# IntegratedSensor.net
KiCad netlist of a schematic drawn in EAGLE
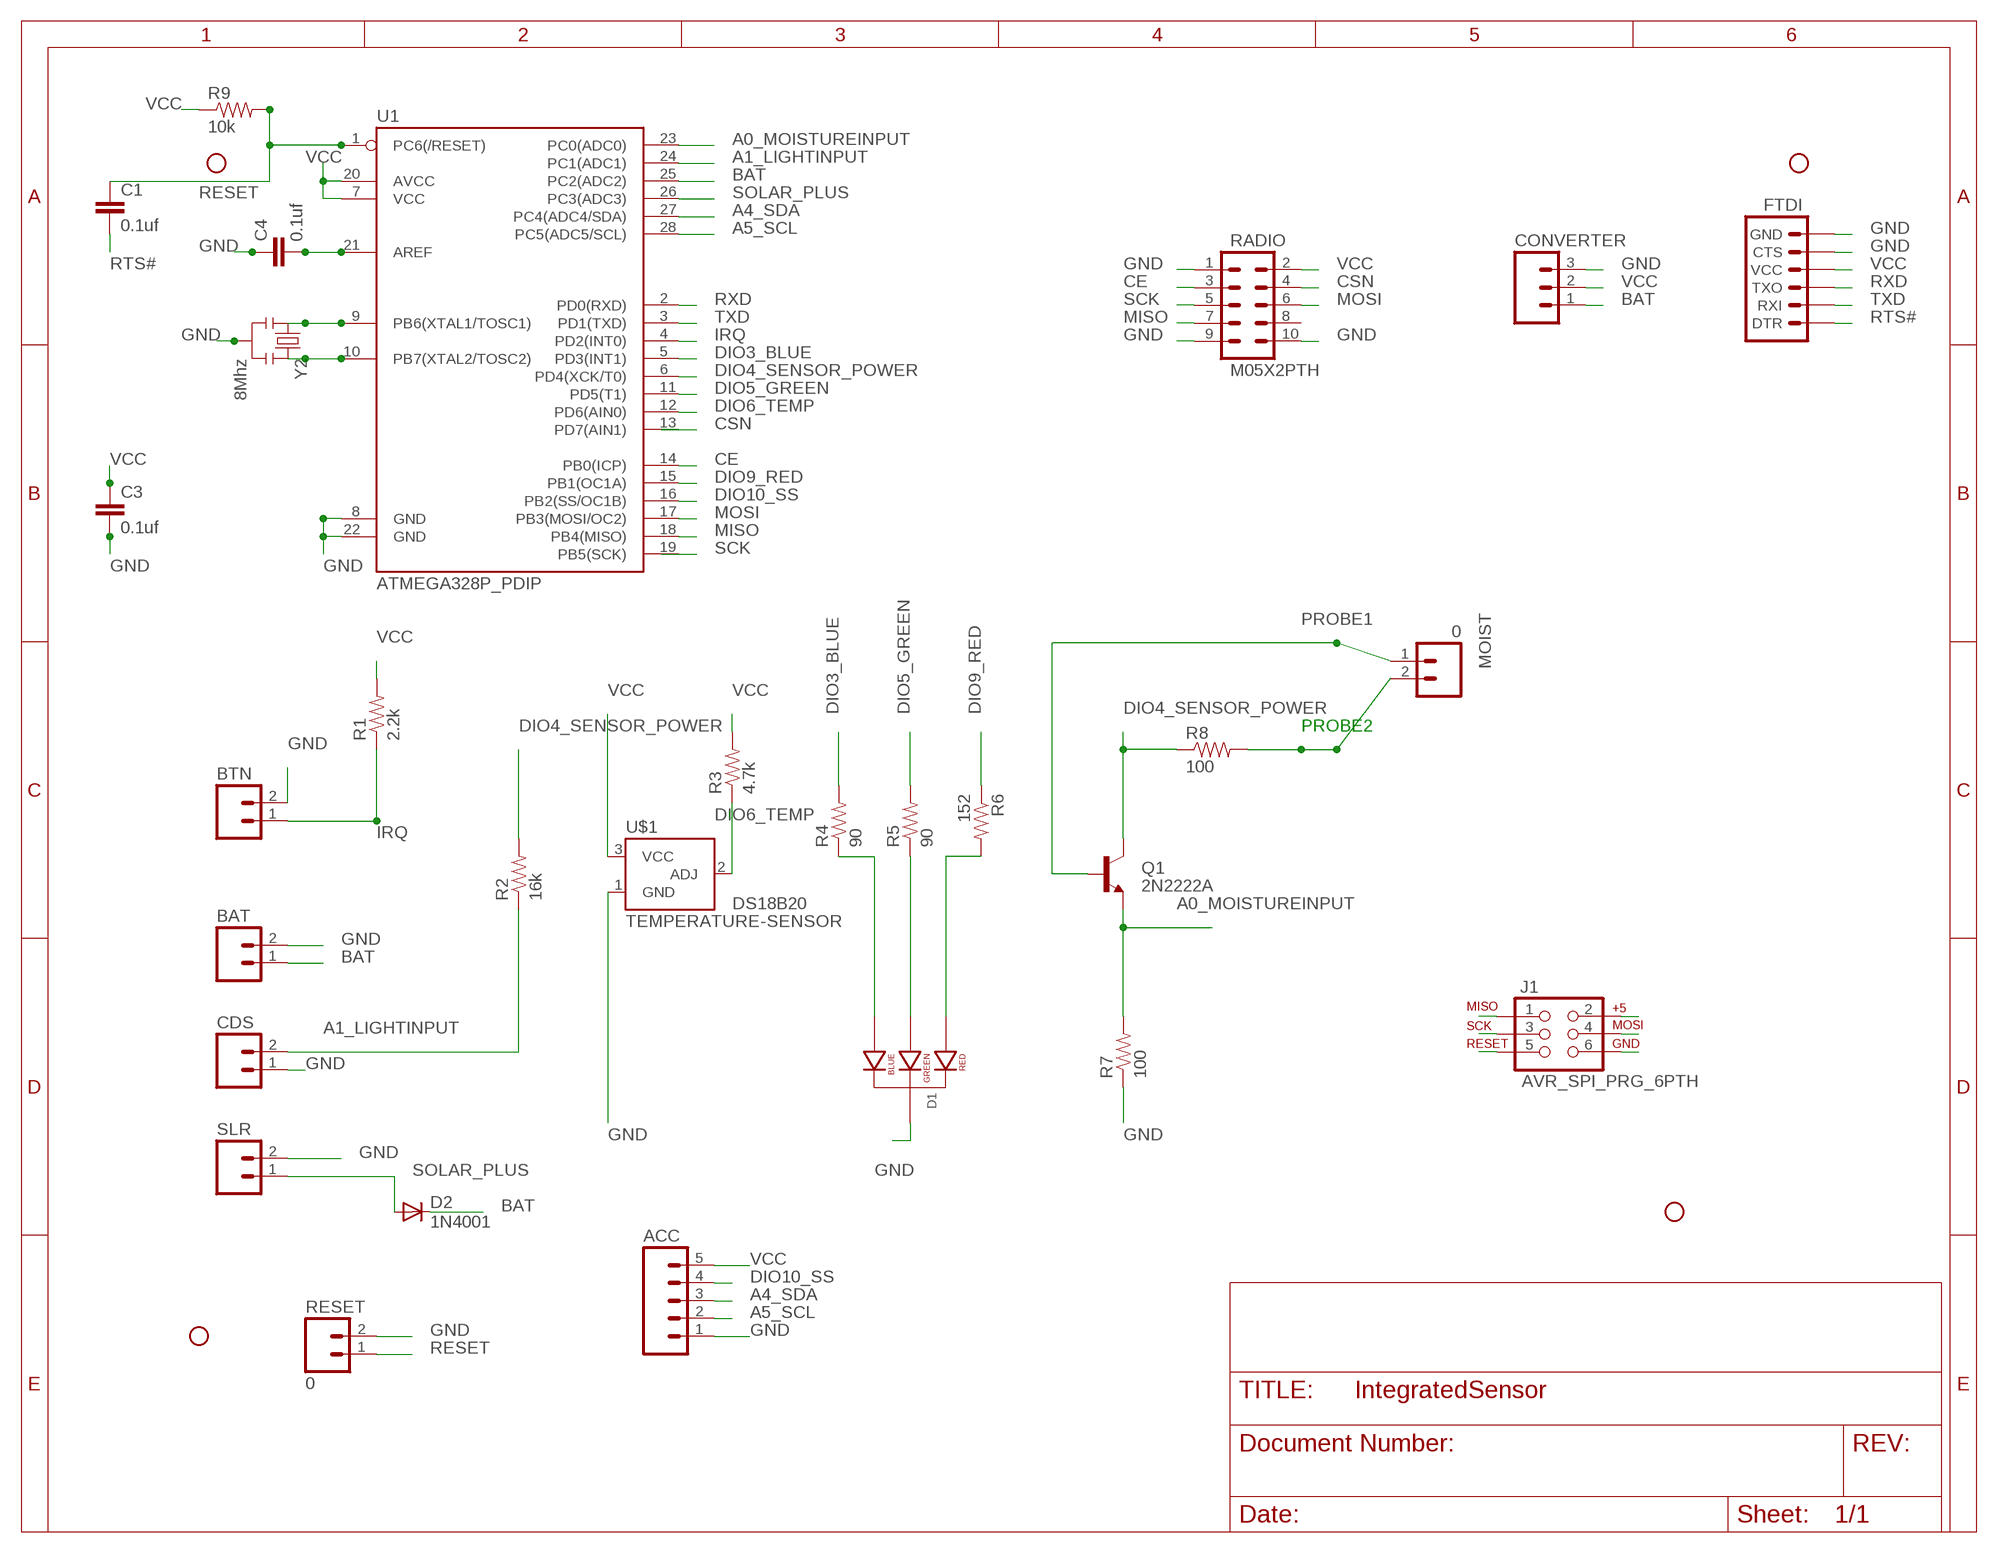
[diagram p0: schematic, sheet 1]

(export (version "E")
  (design (tool "Eeschema 10.0.6"))
  (components
    (comp (ref "ACC")
      (value "M05PTH")
      (footprint "eagle-import:1X05")
      (libsource (lib "eagle-import") (part "M05PTH"))
    )
    (comp (ref "BAT")
      (value "M02PTH")
      (footprint "eagle-import:1X02")
      (libsource (lib "eagle-import") (part "M02PTH"))
    )
    (comp (ref "BTN")
      (value "M02PTH")
      (footprint "eagle-import:1X02")
      (libsource (lib "eagle-import") (part "M02PTH"))
    )
    (comp (ref "C1")
      (value "0.1uf")
      (footprint "eagle-import:CAP-PTH-SMALL")
      (libsource (lib "eagle-import") (part "CAPPTH"))
    )
    (comp (ref "C3")
      (value "0.1uf")
      (footprint "eagle-import:CAP-PTH-SMALL")
      (libsource (lib "eagle-import") (part "CAPPTH"))
    )
    (comp (ref "C4")
      (value "0.1uf")
      (footprint "eagle-import:CAP-PTH-SMALL")
      (libsource (lib "eagle-import") (part "CAPPTH"))
    )
    (comp (ref "CDS")
      (value "M02PTH")
      (footprint "eagle-import:1X02")
      (libsource (lib "eagle-import") (part "M02PTH"))
    )
    (comp (ref "CONVERTER")
      (value "M03PTH")
      (footprint "eagle-import:1X03")
      (libsource (lib "eagle-import") (part "M03PTH"))
    )
    (comp (ref "D1")
      (value "LED-RGB-CC-THRUCLEAR")
      (footprint "eagle-import:LED-RGB-THRU")
      (libsource (lib "eagle-import") (part "LED-RGB-CC-THRUCLEAR"))
    )
    (comp (ref "D2")
      (value "1N4001")
      (footprint "eagle-import:DIODE-1N4001")
      (libsource (lib "eagle-import") (part "DIODEPTH"))
    )
    (comp (ref "FTDI")
      (value "ARDUINO_SERIAL_PROGRAMPTH")
      (footprint "eagle-import:1X06")
      (libsource (lib "eagle-import") (part "ARDUINO_SERIAL_PROGRAMPTH"))
    )
    (comp (ref "J1")
      (value "AVR_SPI_PRG_6PTH")
      (footprint "eagle-import:2X3")
      (libsource (lib "eagle-import") (part "AVR_SPI_PRG_6PTH"))
    )
    (comp (ref "MOIST")
      (value "0")
      (footprint "eagle-import:1X02")
      (libsource (lib "eagle-import") (part "M02PTH"))
    )
    (comp (ref "Q1")
      (value "2N2222A")
      (footprint "eagle-import:TO-92-AMMO")
      (libsource (lib "eagle-import") (part "TRANSISTOR_NPNTO-92-AMMO"))
    )
    (comp (ref "R1")
      (value "2.2k")
      (footprint "eagle-import:1_6W-RES")
      (libsource (lib "eagle-import") (part "RESISTORPTH-1/6W"))
    )
    (comp (ref "R2")
      (value "16k")
      (footprint "eagle-import:1_6W-RES")
      (libsource (lib "eagle-import") (part "RESISTORPTH-1/6W"))
    )
    (comp (ref "R3")
      (value "4.7k")
      (footprint "eagle-import:1_6W-RES")
      (libsource (lib "eagle-import") (part "RESISTORPTH-1/6W"))
    )
    (comp (ref "R4")
      (value "90")
      (footprint "eagle-import:1_6W-RES")
      (libsource (lib "eagle-import") (part "RESISTORPTH-1/6W"))
    )
    (comp (ref "R5")
      (value "90")
      (footprint "eagle-import:1_6W-RES")
      (libsource (lib "eagle-import") (part "RESISTORPTH-1/6W"))
    )
    (comp (ref "R6")
      (value "152")
      (footprint "eagle-import:1_6W-RES")
      (libsource (lib "eagle-import") (part "RESISTORPTH-1/6W"))
    )
    (comp (ref "R7")
      (value "100")
      (footprint "eagle-import:1_6W-RES")
      (libsource (lib "eagle-import") (part "RESISTORPTH-1/6W"))
    )
    (comp (ref "R8")
      (value "100")
      (footprint "eagle-import:1_6W-RES")
      (libsource (lib "eagle-import") (part "RESISTORPTH-1/6W"))
    )
    (comp (ref "R9")
      (value "10k")
      (footprint "eagle-import:1_6W-RES")
      (libsource (lib "eagle-import") (part "RESISTORPTH-1/6W"))
    )
    (comp (ref "RADIO")
      (value "M05X2PTH")
      (footprint "eagle-import:AVR_ICSP")
      (libsource (lib "eagle-import") (part "M05X2PTH"))
    )
    (comp (ref "RESET")
      (value "0")
      (footprint "eagle-import:1X02")
      (libsource (lib "eagle-import") (part "M02PTH"))
    )
    (comp (ref "SLR")
      (value "M02PTH")
      (footprint "eagle-import:1X02")
      (libsource (lib "eagle-import") (part "M02PTH"))
    )
    (comp (ref "STANDOFF1")
      (value "STAND-OFF")
      (footprint "eagle-import:STAND-OFF")
      (libsource (lib "eagle-import") (part "STAND-OFF"))
    )
    (comp (ref "STANDOFF2")
      (value "STAND-OFF")
      (footprint "eagle-import:STAND-OFF")
      (libsource (lib "eagle-import") (part "STAND-OFF"))
    )
    (comp (ref "STANDOFF3")
      (value "STAND-OFF")
      (footprint "eagle-import:STAND-OFF")
      (libsource (lib "eagle-import") (part "STAND-OFF"))
    )
    (comp (ref "STANDOFF4")
      (value "STAND-OFF")
      (footprint "eagle-import:STAND-OFF")
      (libsource (lib "eagle-import") (part "STAND-OFF"))
    )
    (comp (ref "U$1")
      (value "TEMPERATURE-SENSOR")
      (footprint "eagle-import:TO-92")
      (fields (field (name "PARTNAME") "DS18B20"))
      (libsource (lib "eagle-import") (part "TEMPERATURE-SENSOR"))
    )
    (comp (ref "U1")
      (value "ATMEGA328P_PDIP")
      (footprint "eagle-import:DIL28-3")
      (libsource (lib "eagle-import") (part "ATMEGA328P_PDIP"))
    )
    (comp (ref "Y2")
      (value "8Mhz")
      (footprint "eagle-import:RESONATOR-PTH")
      (libsource (lib "eagle-import") (part "RESONATORPTH"))
    )
  )
  (nets
    (net (code "1") (name "/A0_MOISTUREINPUT") (class "Default")
      (node (ref "Q1") (pin "1") (pinfunction "E_1") (pintype "passive"))
      (node (ref "R7") (pin "2") (pinfunction "2_2") (pintype "passive"))
      (node (ref "U1") (pin "23") (pinfunction "PC0(ADC0)_23") (pintype "bidirectional"))
    )
    (net (code "2") (name "/A1_LIGHTINPUT") (class "Default")
      (node (ref "CDS") (pin "2") (pinfunction "2_2") (pintype "passive"))
      (node (ref "R2") (pin "1") (pinfunction "1_1") (pintype "passive"))
      (node (ref "U1") (pin "24") (pinfunction "PC1(ADC1)_24") (pintype "bidirectional"))
    )
    (net (code "3") (name "/A4_SDA") (class "Default")
      (node (ref "ACC") (pin "3") (pinfunction "3_3") (pintype "passive"))
      (node (ref "U1") (pin "27") (pinfunction "PC4(ADC4/SDA)_27") (pintype "bidirectional"))
    )
    (net (code "4") (name "/A5_SCL") (class "Default")
      (node (ref "ACC") (pin "2") (pinfunction "2_2") (pintype "passive"))
      (node (ref "U1") (pin "28") (pinfunction "PC5(ADC5/SCL)_28") (pintype "bidirectional"))
    )
    (net (code "5") (name "/BAT") (class "Default")
      (node (ref "BAT") (pin "1") (pinfunction "1_1") (pintype "passive"))
      (node (ref "CONVERTER") (pin "1") (pinfunction "1_1") (pintype "passive"))
      (node (ref "D2") (pin "C") (pinfunction "C_C") (pintype "passive"))
      (node (ref "U1") (pin "25") (pinfunction "PC2(ADC2)_25") (pintype "bidirectional"))
    )
    (net (code "6") (name "/CE") (class "Default")
      (node (ref "RADIO") (pin "3") (pinfunction "3_3") (pintype "passive"))
      (node (ref "U1") (pin "14") (pinfunction "PB0(ICP)_14") (pintype "bidirectional"))
    )
    (net (code "7") (name "/CSN") (class "Default")
      (node (ref "RADIO") (pin "4") (pinfunction "4_4") (pintype "passive"))
    )
    (net (code "8") (name "/DIO3_BLUE") (class "Default")
      (node (ref "R4") (pin "2") (pinfunction "2_2") (pintype "passive"))
      (node (ref "U1") (pin "5") (pinfunction "PD3(INT1)_5") (pintype "bidirectional"))
    )
    (net (code "9") (name "/DIO4_SENSOR_POWER") (class "Default")
      (node (ref "Q1") (pin "3") (pinfunction "C_3") (pintype "passive"))
      (node (ref "R2") (pin "2") (pinfunction "2_2") (pintype "passive"))
      (node (ref "R8") (pin "1") (pinfunction "1_1") (pintype "passive"))
      (node (ref "U1") (pin "6") (pinfunction "PD4(XCK/T0)_6") (pintype "bidirectional"))
    )
    (net (code "10") (name "/DIO5_GREEN") (class "Default")
      (node (ref "R5") (pin "2") (pinfunction "2_2") (pintype "passive"))
      (node (ref "U1") (pin "11") (pinfunction "PD5(T1)_11") (pintype "bidirectional"))
    )
    (net (code "11") (name "/DIO6_TEMP") (class "Default")
      (node (ref "R3") (pin "1") (pinfunction "1_1") (pintype "passive"))
      (node (ref "U$1") (pin "2") (pinfunction "ADJ_2") (pintype "bidirectional"))
      (node (ref "U1") (pin "12") (pinfunction "PD6(AIN0)_12") (pintype "bidirectional"))
    )
    (net (code "12") (name "/DIO9_RED") (class "Default")
      (node (ref "R6") (pin "1") (pinfunction "1_1") (pintype "passive"))
      (node (ref "U1") (pin "15") (pinfunction "PB1(OC1A)_15") (pintype "bidirectional"))
    )
    (net (code "13") (name "/DIO10_SS") (class "Default")
      (node (ref "ACC") (pin "4") (pinfunction "4_4") (pintype "passive"))
      (node (ref "U1") (pin "16") (pinfunction "PB2(SS/OC1B)_16") (pintype "bidirectional"))
    )
    (net (code "14") (name "/GND") (class "Default")
      (node (ref "ACC") (pin "1") (pinfunction "1_1") (pintype "passive"))
      (node (ref "BAT") (pin "2") (pinfunction "2_2") (pintype "passive"))
      (node (ref "BTN") (pin "2") (pinfunction "2_2") (pintype "passive"))
      (node (ref "C3") (pin "2") (pinfunction "2_2") (pintype "passive"))
      (node (ref "C4") (pin "1") (pinfunction "1_1") (pintype "passive"))
      (node (ref "CDS") (pin "1") (pinfunction "1_1") (pintype "passive"))
      (node (ref "CONVERTER") (pin "3") (pinfunction "3_3") (pintype "passive"))
      (node (ref "D1") (pin "2") (pinfunction "CATHODE_2") (pintype "bidirectional"))
      (node (ref "FTDI") (pin "5") (pinfunction "CTS_5") (pintype "passive"))
      (node (ref "FTDI") (pin "6") (pinfunction "GND_6") (pintype "passive"))
      (node (ref "J1") (pin "6") (pinfunction "6_6") (pintype "passive"))
      (node (ref "R7") (pin "1") (pinfunction "1_1") (pintype "passive"))
      (node (ref "RADIO") (pin "1") (pinfunction "1_1") (pintype "passive"))
      (node (ref "RADIO") (pin "10") (pinfunction "10_10") (pintype "passive"))
      (node (ref "RADIO") (pin "9") (pinfunction "9_9") (pintype "passive"))
      (node (ref "RESET") (pin "2") (pinfunction "2_2") (pintype "passive"))
      (node (ref "SLR") (pin "2") (pinfunction "2_2") (pintype "passive"))
      (node (ref "U$1") (pin "1") (pinfunction "GND_1") (pintype "bidirectional"))
      (node (ref "U1") (pin "22") (pinfunction "GND_22") (pintype "bidirectional"))
      (node (ref "U1") (pin "8") (pinfunction "GND_8") (pintype "bidirectional"))
      (node (ref "Y2") (pin "2") (pinfunction "2_2") (pintype "passive"))
    )
    (net (code "15") (name "/IRQ") (class "Default")
      (node (ref "BTN") (pin "1") (pinfunction "1_1") (pintype "passive"))
      (node (ref "R1") (pin "1") (pinfunction "1_1") (pintype "passive"))
      (node (ref "U1") (pin "4") (pinfunction "PD2(INT0)_4") (pintype "bidirectional"))
    )
    (net (code "16") (name "/MISO") (class "Default")
      (node (ref "J1") (pin "1") (pinfunction "1_1") (pintype "passive"))
      (node (ref "RADIO") (pin "7") (pinfunction "7_7") (pintype "passive"))
      (node (ref "U1") (pin "18") (pinfunction "PB4(MISO)_18") (pintype "bidirectional"))
    )
    (net (code "17") (name "/MOSI") (class "Default")
      (node (ref "J1") (pin "4") (pinfunction "4_4") (pintype "passive"))
      (node (ref "RADIO") (pin "6") (pinfunction "6_6") (pintype "passive"))
      (node (ref "U1") (pin "17") (pinfunction "PB3(MOSI/OC2)_17") (pintype "bidirectional"))
    )
    (net (code "18") (name "/PROBE1") (class "Default")
      (node (ref "MOIST") (pin "1") (pinfunction "1_1") (pintype "passive"))
      (node (ref "Q1") (pin "2") (pinfunction "B_2") (pintype "passive"))
    )
    (net (code "19") (name "/PROBE2") (class "Default")
      (node (ref "MOIST") (pin "2") (pinfunction "2_2") (pintype "passive"))
      (node (ref "R8") (pin "2") (pinfunction "2_2") (pintype "passive"))
    )
    (net (code "20") (name "/RESET") (class "Default")
      (node (ref "C1") (pin "1") (pinfunction "1_1") (pintype "passive"))
      (node (ref "J1") (pin "5") (pinfunction "5_5") (pintype "passive"))
      (node (ref "R9") (pin "2") (pinfunction "2_2") (pintype "passive"))
      (node (ref "RESET") (pin "1") (pinfunction "1_1") (pintype "passive"))
      (node (ref "U1") (pin "1") (pinfunction "PC6(/RESET)_1") (pintype "bidirectional"))
    )
    (net (code "21") (name "/RTS#") (class "Default")
      (node (ref "C1") (pin "2") (pinfunction "2_2") (pintype "passive"))
      (node (ref "FTDI") (pin "1") (pinfunction "DTR_1") (pintype "passive"))
    )
    (net (code "22") (name "/RXD") (class "Default")
      (node (ref "FTDI") (pin "3") (pinfunction "TXO_3") (pintype "passive"))
      (node (ref "U1") (pin "2") (pinfunction "PD0(RXD)_2") (pintype "bidirectional"))
    )
    (net (code "23") (name "/SCK") (class "Default")
      (node (ref "J1") (pin "3") (pinfunction "3_3") (pintype "passive"))
      (node (ref "RADIO") (pin "5") (pinfunction "5_5") (pintype "passive"))
    )
    (net (code "24") (name "/SOLAR_PLUS") (class "Default")
      (node (ref "D2") (pin "A") (pinfunction "A_A") (pintype "passive"))
      (node (ref "SLR") (pin "1") (pinfunction "1_1") (pintype "passive"))
      (node (ref "U1") (pin "26") (pinfunction "PC3(ADC3)_26") (pintype "bidirectional"))
    )
    (net (code "25") (name "/TXD") (class "Default")
      (node (ref "FTDI") (pin "2") (pinfunction "RXI_2") (pintype "passive"))
      (node (ref "U1") (pin "3") (pinfunction "PD1(TXD)_3") (pintype "bidirectional"))
    )
    (net (code "26") (name "/VCC") (class "Default")
      (node (ref "ACC") (pin "5") (pinfunction "5_5") (pintype "passive"))
      (node (ref "C3") (pin "1") (pinfunction "1_1") (pintype "passive"))
      (node (ref "CONVERTER") (pin "2") (pinfunction "2_2") (pintype "passive"))
      (node (ref "FTDI") (pin "4") (pinfunction "VCC_4") (pintype "passive"))
      (node (ref "J1") (pin "2") (pinfunction "2_2") (pintype "passive"))
      (node (ref "R1") (pin "2") (pinfunction "2_2") (pintype "passive"))
      (node (ref "R3") (pin "2") (pinfunction "2_2") (pintype "passive"))
      (node (ref "R9") (pin "1") (pinfunction "1_1") (pintype "passive"))
      (node (ref "RADIO") (pin "2") (pinfunction "2_2") (pintype "passive"))
      (node (ref "U$1") (pin "3") (pinfunction "VCC_3") (pintype "bidirectional"))
      (node (ref "U1") (pin "20") (pinfunction "AVCC_20") (pintype "bidirectional"))
      (node (ref "U1") (pin "7") (pinfunction "VCC_7") (pintype "bidirectional"))
    )
    (net (code "27") (name "Net-(D1-BLUE_CATHODE)") (class "Default")
      (node (ref "D1") (pin "4") (pinfunction "BLUE_CATHODE_4") (pintype "bidirectional"))
      (node (ref "R4") (pin "1") (pinfunction "1_1") (pintype "passive"))
    )
    (net (code "28") (name "Net-(D1-GREEN_CATHODE)") (class "Default")
      (node (ref "D1") (pin "3") (pinfunction "GREEN_CATHODE_3") (pintype "bidirectional"))
      (node (ref "R5") (pin "1") (pinfunction "1_1") (pintype "passive"))
    )
    (net (code "29") (name "Net-(D1-RED_CATHODE)") (class "Default")
      (node (ref "D1") (pin "1") (pinfunction "RED_CATHODE_1") (pintype "bidirectional"))
      (node (ref "R6") (pin "2") (pinfunction "2_2") (pintype "passive"))
    )
    (net (code "30") (name "Net-(U1-AREF)") (class "Default")
      (node (ref "C4") (pin "2") (pinfunction "2_2") (pintype "passive"))
      (node (ref "U1") (pin "21") (pinfunction "AREF_21") (pintype "bidirectional"))
    )
    (net (code "31") (name "Net-(U1-PB6(XTAL1{slash}TOSC1))") (class "Default")
      (node (ref "U1") (pin "9") (pinfunction "PB6(XTAL1/TOSC1)_9") (pintype "bidirectional"))
      (node (ref "Y2") (pin "1") (pinfunction "1_1") (pintype "passive"))
    )
    (net (code "32") (name "Net-(U1-PB7(XTAL2{slash}TOSC2))") (class "Default")
      (node (ref "U1") (pin "10") (pinfunction "PB7(XTAL2/TOSC2)_10") (pintype "bidirectional"))
      (node (ref "Y2") (pin "3") (pinfunction "3_3") (pintype "passive"))
    )
    (net (code "33") (name "unconnected-(RADIO-Pad8)") (class "Default")
      (node (ref "RADIO") (pin "8") (pinfunction "8_8") (pintype "passive"))
    )
    (net (code "34") (name "unconnected-(U1-PB5(SCK)-Pad19)") (class "Default")
      (node (ref "U1") (pin "19") (pinfunction "PB5(SCK)_19") (pintype "bidirectional"))
    )
    (net (code "35") (name "unconnected-(U1-PD7(AIN1)-Pad13)") (class "Default")
      (node (ref "U1") (pin "13") (pinfunction "PD7(AIN1)_13") (pintype "bidirectional"))
    )
  )
)
